# samd21_QFP_reference.net
KiCad netlist of a schematic drawn in EAGLE
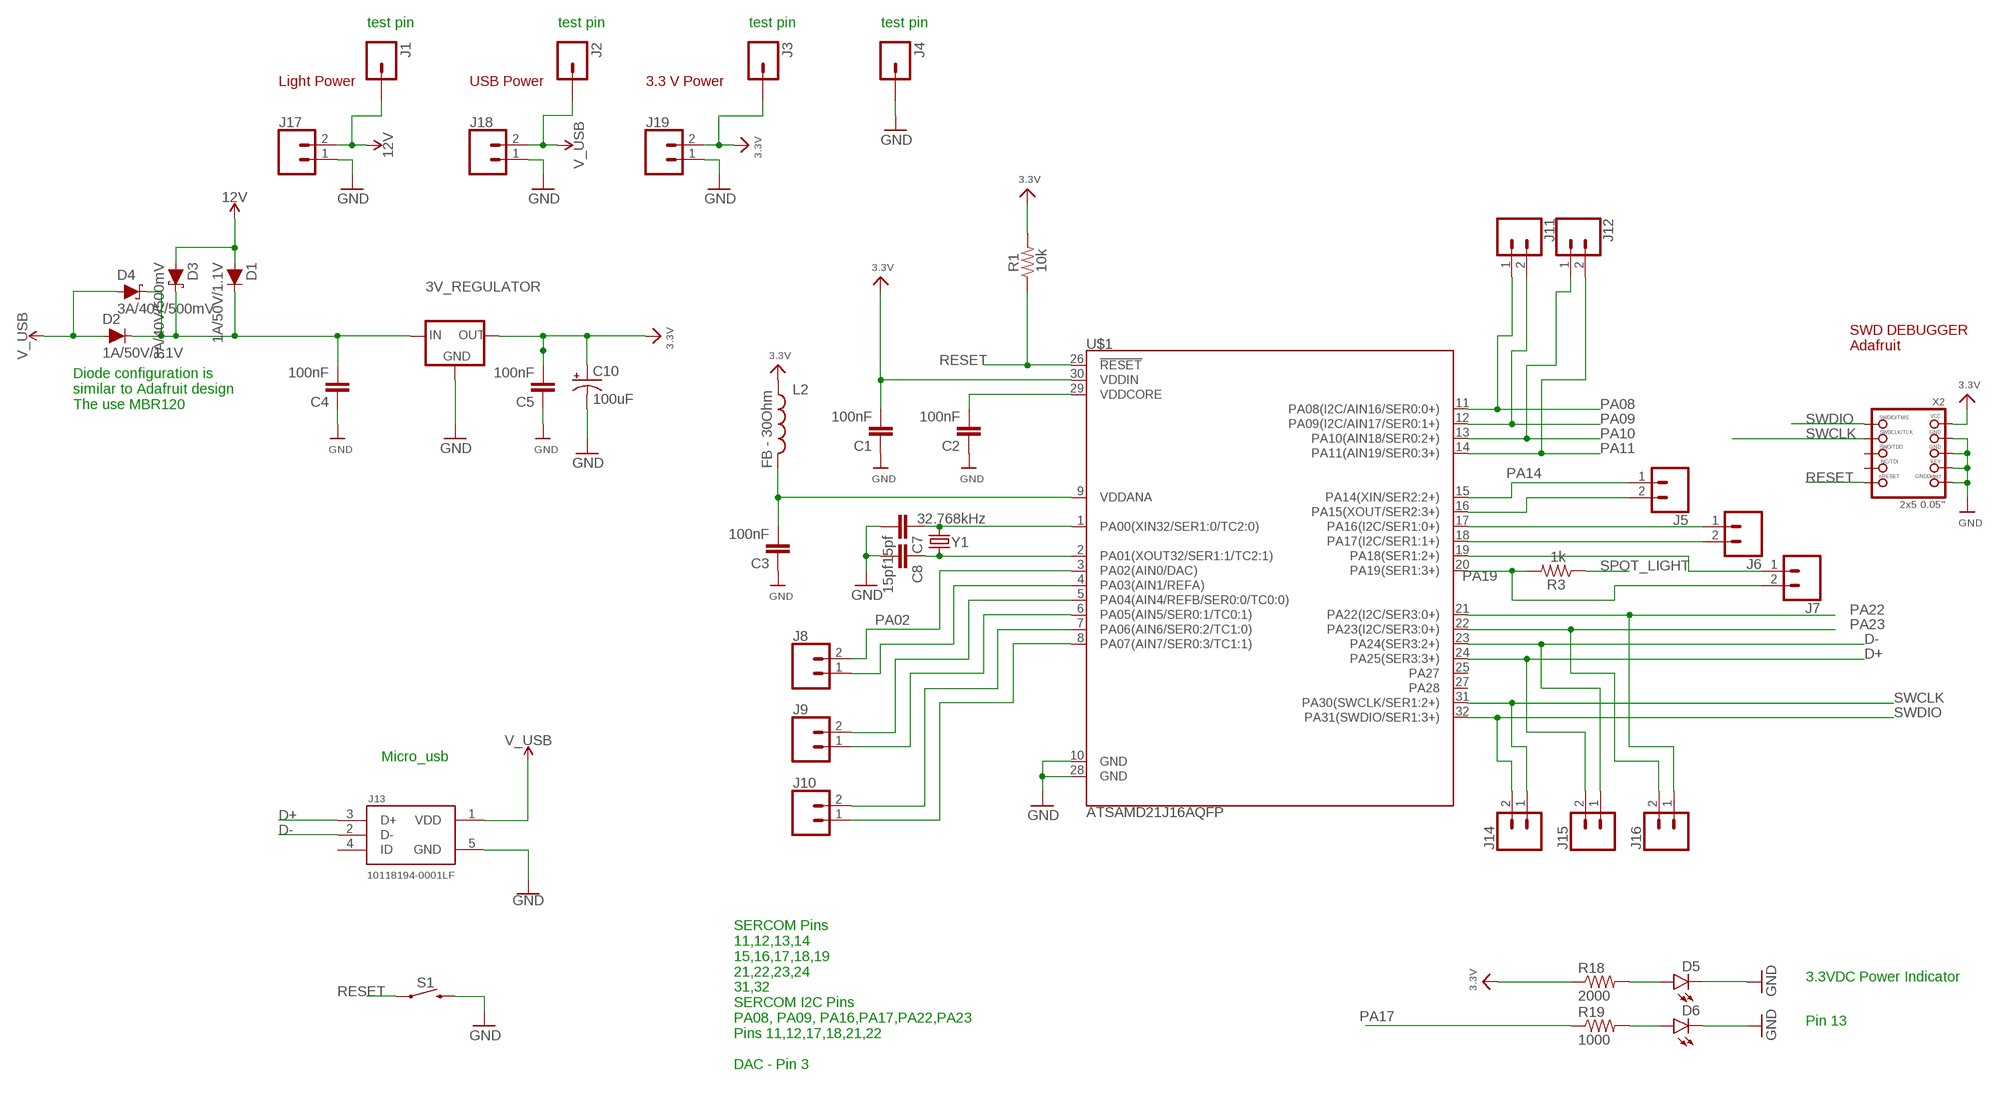
[diagram p0: schematic, sheet 1, part 1 of 2]
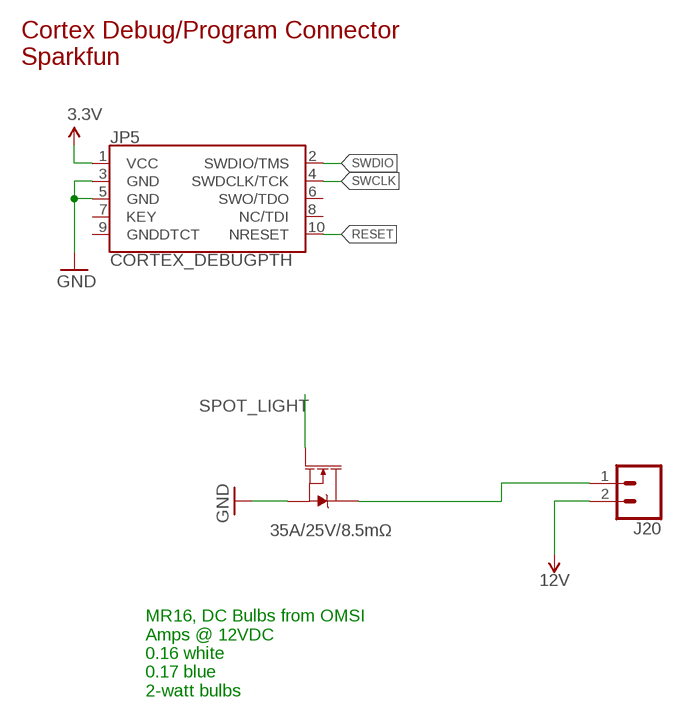
[diagram p1: schematic, sheet 1, part 2 of 2]

(export (version "E")
  (design (tool "Eeschema 10.0.6"))
  (components
    (comp (ref "3V_REGULATOR")
      (value "LDL1117_5V_REG")
      (footprint "eagle-import:SOT223")
      (libsource (lib "eagle-import") (part "LDL1117_5V_REG"))
    )
    (comp (ref "C1")
      (value "100nF")
      (footprint "eagle-import:0805")
      (libsource (lib "eagle-import") (part "10UF-0805-10V-10%"))
    )
    (comp (ref "C2")
      (value "100nF")
      (footprint "eagle-import:0805")
      (libsource (lib "eagle-import") (part "10UF-0805-10V-10%"))
    )
    (comp (ref "C3")
      (value "100nF")
      (footprint "eagle-import:0805")
      (libsource (lib "eagle-import") (part "10UF-0805-10V-10%"))
    )
    (comp (ref "C4")
      (value "100nF")
      (footprint "eagle-import:0805")
      (libsource (lib "eagle-import") (part "10UF-0805-10V-10%"))
    )
    (comp (ref "C5")
      (value "100nF")
      (footprint "eagle-import:0805")
      (libsource (lib "eagle-import") (part "10UF-0805-10V-10%"))
    )
    (comp (ref "C7")
      (value "15pf")
      (footprint "eagle-import:0805")
      (libsource (lib "eagle-import") (part "10UF-0805-10V-10%"))
    )
    (comp (ref "C8")
      (value "15pf")
      (footprint "eagle-import:0805")
      (libsource (lib "eagle-import") (part "10UF-0805-10V-10%"))
    )
    (comp (ref "C10")
      (value "100uF")
      (footprint "eagle-import:CPOL-RADIAL-2.5MM-6.5MM")
      (libsource (lib "eagle-import") (part "100UF-POLAR-RADIAL-2.5MM-25V-20%"))
    )
    (comp (ref "D1")
      (value "1A/50V/1.1V")
      (footprint "eagle-import:DIODE-1N4001")
      (libsource (lib "eagle-import") (part "DIODE-PTH"))
    )
    (comp (ref "D2")
      (value "1A/50V/1.1V")
      (footprint "eagle-import:DIODE-1N4001")
      (libsource (lib "eagle-import") (part "DIODE-PTH"))
    )
    (comp (ref "D3")
      (value "3A/40V/500mV")
      (footprint "eagle-import:SMA-DIODE")
      (libsource (lib "eagle-import") (part "DIODE-SCHOTTKY-B340A"))
    )
    (comp (ref "D4")
      (value "3A/40V/500mV")
      (footprint "eagle-import:SMA-DIODE")
      (libsource (lib "eagle-import") (part "DIODE-SCHOTTKY-B340A"))
    )
    (comp (ref "D5")
      (value "LED1206")
      (footprint "eagle-import:LED-1206")
      (libsource (lib "eagle-import") (part "LED1206"))
    )
    (comp (ref "D6")
      (value "LED1206")
      (footprint "eagle-import:LED-1206")
      (libsource (lib "eagle-import") (part "LED1206"))
    )
    (comp (ref "J1")
      (value "M01PTH")
      (footprint "eagle-import:1X01")
      (libsource (lib "eagle-import") (part "M01PTH"))
    )
    (comp (ref "J2")
      (value "M01PTH")
      (footprint "eagle-import:1X01")
      (libsource (lib "eagle-import") (part "M01PTH"))
    )
    (comp (ref "J3")
      (value "M01PTH")
      (footprint "eagle-import:1X01")
      (libsource (lib "eagle-import") (part "M01PTH"))
    )
    (comp (ref "J4")
      (value "M01PTH")
      (footprint "eagle-import:1X01")
      (libsource (lib "eagle-import") (part "M01PTH"))
    )
    (comp (ref "J5")
      (value "CONN_025MM")
      (footprint "eagle-import:SCREWTERMINAL-5MM-2")
      (libsource (lib "eagle-import") (part "CONN_025MM"))
    )
    (comp (ref "J6")
      (value "CONN_025MM")
      (footprint "eagle-import:SCREWTERMINAL-5MM-2")
      (libsource (lib "eagle-import") (part "CONN_025MM"))
    )
    (comp (ref "J7")
      (value "CONN_025MM")
      (footprint "eagle-import:SCREWTERMINAL-5MM-2")
      (libsource (lib "eagle-import") (part "CONN_025MM"))
    )
    (comp (ref "J8")
      (value "CONN_025MM")
      (footprint "eagle-import:SCREWTERMINAL-5MM-2")
      (libsource (lib "eagle-import") (part "CONN_025MM"))
    )
    (comp (ref "J9")
      (value "CONN_025MM")
      (footprint "eagle-import:SCREWTERMINAL-5MM-2")
      (libsource (lib "eagle-import") (part "CONN_025MM"))
    )
    (comp (ref "J10")
      (value "CONN_025MM")
      (footprint "eagle-import:SCREWTERMINAL-5MM-2")
      (libsource (lib "eagle-import") (part "CONN_025MM"))
    )
    (comp (ref "J11")
      (value "CONN_025MM")
      (footprint "eagle-import:SCREWTERMINAL-5MM-2")
      (libsource (lib "eagle-import") (part "CONN_025MM"))
    )
    (comp (ref "J12")
      (value "CONN_025MM")
      (footprint "eagle-import:SCREWTERMINAL-5MM-2")
      (libsource (lib "eagle-import") (part "CONN_025MM"))
    )
    (comp (ref "J13")
      (value "10118194-0001LF")
      (footprint "eagle-import:FRAMATOME_10118194-0001LF")
      (fields (field (name "MF") "Amphenol ICC"))
      (libsource (lib "eagle-import") (part "10118194-0001LF"))
    )
    (comp (ref "J14")
      (value "CONN_025MM")
      (footprint "eagle-import:SCREWTERMINAL-5MM-2")
      (libsource (lib "eagle-import") (part "CONN_025MM"))
    )
    (comp (ref "J15")
      (value "CONN_025MM")
      (footprint "eagle-import:SCREWTERMINAL-5MM-2")
      (libsource (lib "eagle-import") (part "CONN_025MM"))
    )
    (comp (ref "J16")
      (value "CONN_025MM")
      (footprint "eagle-import:SCREWTERMINAL-5MM-2")
      (libsource (lib "eagle-import") (part "CONN_025MM"))
    )
    (comp (ref "J17")
      (value "CONN_025MM")
      (footprint "eagle-import:SCREWTERMINAL-5MM-2")
      (libsource (lib "eagle-import") (part "CONN_025MM"))
    )
    (comp (ref "J18")
      (value "CONN_025MM")
      (footprint "eagle-import:SCREWTERMINAL-5MM-2")
      (libsource (lib "eagle-import") (part "CONN_025MM"))
    )
    (comp (ref "J19")
      (value "CONN_025MM")
      (footprint "eagle-import:SCREWTERMINAL-5MM-2")
      (libsource (lib "eagle-import") (part "CONN_025MM"))
    )
    (comp (ref "J20")
      (value "CONN_025MM")
      (footprint "eagle-import:SCREWTERMINAL-5MM-2")
      (libsource (lib "eagle-import") (part "CONN_025MM"))
    )
    (comp (ref "JP5")
      (value "CORTEX_DEBUGPTH")
      (footprint "eagle-import:2X5-PTH-1.27MM")
      (libsource (lib "eagle-import") (part "CORTEX_DEBUGPTH"))
    )
    (comp (ref "L2")
      (value "FB - 30Ohm")
      (footprint "eagle-import:0805@1")
      (libsource (lib "eagle-import") (part "INDUCTOR0805"))
    )
    (comp (ref "Q1")
      (value "35A/25V/8.5mΩ")
      (footprint "eagle-import:DPAK")
      (libsource (lib "eagle-import") (part "MOSFET-NCH-FDD8780"))
    )
    (comp (ref "R1")
      (value "10k")
      (footprint "eagle-import:0805")
      (libsource (lib "eagle-import") (part "RESISTOR0805"))
    )
    (comp (ref "R3")
      (value "1k")
      (footprint "eagle-import:0805")
      (libsource (lib "eagle-import") (part "RESISTOR0805"))
    )
    (comp (ref "R18")
      (value "2000")
      (footprint "eagle-import:0805")
      (libsource (lib "eagle-import") (part "RESISTOR0805-RES"))
    )
    (comp (ref "R19")
      (value "1000")
      (footprint "eagle-import:0805")
      (libsource (lib "eagle-import") (part "RESISTOR0805-RES"))
    )
    (comp (ref "S1")
      (value "MOMENTARY-SWITCH-SPST-PTH-6.0MM-KIT")
      (footprint "eagle-import:TACTILE_SWITCH_PTH_6.0MM_KIT")
      (libsource (lib "eagle-import") (part "MOMENTARY-SWITCH-SPST-PTH-6.0MM-KIT"))
    )
    (comp (ref "U$1")
      (value "ATSAMD21J16AQFP")
      (footprint "eagle-import:TQFP32-08")
      (libsource (lib "eagle-import") (part "ATSAMD21J16AQFP"))
    )
    (comp (ref "X2")
      (value "2x5 0.05\"")
      (footprint "eagle-import:2X05_1.27MM_BOX_POSTS")
      (libsource (lib "eagle-import") (part "JTAG-CORTEXBOXPOSTS"))
    )
    (comp (ref "Y1")
      (value "32.768kHz")
      (footprint "eagle-import:CRYSTAL-SMD-3.2X1.5MM")
      (libsource (lib "eagle-import") (part "CRYSTAL3.2X1.5MM"))
    )
  )
  (nets
    (net (code "1") (name "/D+") (class "Default")
      (node (ref "J13") (pin "3") (pinfunction "D+_3") (pintype "bidirectional"))
      (node (ref "J15") (pin "2") (pinfunction "2_2") (pintype "passive"))
      (node (ref "U$1") (pin "24") (pinfunction "PA25(SER3:3+)_24") (pintype "bidirectional"))
    )
    (net (code "2") (name "/D-") (class "Default")
      (node (ref "J13") (pin "2") (pinfunction "D-_2") (pintype "bidirectional"))
      (node (ref "J15") (pin "1") (pinfunction "1_1") (pintype "passive"))
      (node (ref "U$1") (pin "23") (pinfunction "PA24(SER3:2+)_23") (pintype "bidirectional"))
    )
    (net (code "3") (name "/PA02") (class "Default")
      (node (ref "J8") (pin "2") (pinfunction "2_2") (pintype "passive"))
      (node (ref "U$1") (pin "3") (pinfunction "PA02(AIN0/DAC)_3") (pintype "bidirectional"))
    )
    (net (code "4") (name "/PA08") (class "Default")
      (node (ref "J11") (pin "1") (pinfunction "1_1") (pintype "passive"))
      (node (ref "U$1") (pin "11") (pinfunction "PA08(I2C/AIN16/SER0:0+)_11") (pintype "bidirectional"))
    )
    (net (code "5") (name "/PA09") (class "Default")
      (node (ref "J11") (pin "2") (pinfunction "2_2") (pintype "passive"))
      (node (ref "U$1") (pin "12") (pinfunction "PA09(I2C/AIN17/SER0:1+)_12") (pintype "bidirectional"))
    )
    (net (code "6") (name "/PA10") (class "Default")
      (node (ref "J12") (pin "1") (pinfunction "1_1") (pintype "passive"))
      (node (ref "U$1") (pin "13") (pinfunction "PA10(AIN18/SER0:2+)_13") (pintype "bidirectional"))
    )
    (net (code "7") (name "/PA11") (class "Default")
      (node (ref "J12") (pin "2") (pinfunction "2_2") (pintype "passive"))
      (node (ref "U$1") (pin "14") (pinfunction "PA11(AIN19/SER0:3+)_14") (pintype "bidirectional"))
    )
    (net (code "8") (name "/PA14") (class "Default")
      (node (ref "J5") (pin "1") (pinfunction "1_1") (pintype "passive"))
      (node (ref "U$1") (pin "15") (pinfunction "PA14(XIN/SER2:2+)_15") (pintype "bidirectional"))
    )
    (net (code "9") (name "/PA17") (class "Default")
      (node (ref "J6") (pin "2") (pinfunction "2_2") (pintype "passive"))
      (node (ref "R19") (pin "1") (pinfunction "1_1") (pintype "passive"))
      (node (ref "U$1") (pin "18") (pinfunction "PA17(I2C/SER1:1+)_18") (pintype "bidirectional"))
    )
    (net (code "10") (name "/PA19") (class "Default")
      (node (ref "J7") (pin "2") (pinfunction "2_2") (pintype "passive"))
      (node (ref "R3") (pin "2") (pinfunction "2_2") (pintype "passive"))
      (node (ref "U$1") (pin "20") (pinfunction "PA19(SER1:3+)_20") (pintype "bidirectional"))
    )
    (net (code "11") (name "/PA22") (class "Default")
      (node (ref "J16") (pin "1") (pinfunction "1_1") (pintype "passive"))
      (node (ref "U$1") (pin "21") (pinfunction "PA22(I2C/SER3:0+)_21") (pintype "bidirectional"))
    )
    (net (code "12") (name "/PA23") (class "Default")
      (node (ref "J16") (pin "2") (pinfunction "2_2") (pintype "passive"))
      (node (ref "U$1") (pin "22") (pinfunction "PA23(I2C/SER3:0+)_22") (pintype "bidirectional"))
    )
    (net (code "13") (name "/SPOT_LIGHT") (class "Default")
      (node (ref "Q1") (pin "1") (pinfunction "G_1") (pintype "bidirectional"))
      (node (ref "R3") (pin "1") (pinfunction "1_1") (pintype "passive"))
    )
    (net (code "14") (name "3.3V") (class "Default")
      (node (ref "3V_REGULATOR") (pin "2") (pinfunction "OUT_2") (pintype "passive"))
      (node (ref "3V_REGULATOR") (pin "4") (pinfunction "OUT_4") (pintype "passive"))
      (node (ref "C1") (pin "2") (pinfunction "2_2") (pintype "passive"))
      (node (ref "C10") (pin "1") (pinfunction "+_1") (pintype "passive"))
      (node (ref "C5") (pin "2") (pinfunction "2_2") (pintype "passive"))
      (node (ref "J19") (pin "2") (pinfunction "2_2") (pintype "passive"))
      (node (ref "J3") (pin "1") (pinfunction "1_1") (pintype "passive"))
      (node (ref "JP5") (pin "1") (pinfunction "VCC_1") (pintype "bidirectional"))
      (node (ref "L2") (pin "1") (pinfunction "1_1") (pintype "passive"))
      (node (ref "R1") (pin "2") (pinfunction "2_2") (pintype "passive"))
      (node (ref "R18") (pin "1") (pinfunction "1_1") (pintype "passive"))
      (node (ref "U$1") (pin "30") (pinfunction "VDDIN_30") (pintype "bidirectional"))
      (node (ref "X2") (pin "1") (pinfunction "VCC_1") (pintype "power_in"))
    )
    (net (code "15") (name "12V") (class "Default")
      (node (ref "D1") (pin "A") (pinfunction "A_A") (pintype "passive"))
      (node (ref "D3") (pin "A") (pinfunction "A_A") (pintype "passive"))
      (node (ref "J1") (pin "1") (pinfunction "1_1") (pintype "passive"))
      (node (ref "J17") (pin "2") (pinfunction "2_2") (pintype "passive"))
      (node (ref "J20") (pin "2") (pinfunction "2_2") (pintype "passive"))
    )
    (net (code "16") (name "GND") (class "Default")
      (node (ref "3V_REGULATOR") (pin "1") (pinfunction "GND_1") (pintype "input"))
      (node (ref "C1") (pin "1") (pinfunction "1_1") (pintype "passive"))
      (node (ref "C10") (pin "2") (pinfunction "-_2") (pintype "passive"))
      (node (ref "C2") (pin "1") (pinfunction "1_1") (pintype "passive"))
      (node (ref "C3") (pin "1") (pinfunction "1_1") (pintype "passive"))
      (node (ref "C4") (pin "1") (pinfunction "1_1") (pintype "passive"))
      (node (ref "C5") (pin "1") (pinfunction "1_1") (pintype "passive"))
      (node (ref "C7") (pin "2") (pinfunction "2_2") (pintype "passive"))
      (node (ref "C8") (pin "2") (pinfunction "2_2") (pintype "passive"))
      (node (ref "D5") (pin "C") (pinfunction "C_C") (pintype "passive"))
      (node (ref "D6") (pin "C") (pinfunction "C_C") (pintype "passive"))
      (node (ref "J13") (pin "5") (pinfunction "GND_5") (pintype "power_in"))
      (node (ref "J17") (pin "1") (pinfunction "1_1") (pintype "passive"))
      (node (ref "J18") (pin "1") (pinfunction "1_1") (pintype "passive"))
      (node (ref "J19") (pin "1") (pinfunction "1_1") (pintype "passive"))
      (node (ref "J4") (pin "1") (pinfunction "1_1") (pintype "passive"))
      (node (ref "JP5") (pin "3") (pinfunction "GND_3") (pintype "bidirectional"))
      (node (ref "JP5") (pin "5") (pinfunction "GND_5") (pintype "bidirectional"))
      (node (ref "Q1") (pin "3") (pinfunction "S_3") (pintype "bidirectional"))
      (node (ref "S1") (pin "3") (pinfunction "2_3") (pintype "passive"))
      (node (ref "U$1") (pin "10") (pinfunction "GND_10") (pintype "bidirectional"))
      (node (ref "U$1") (pin "28") (pinfunction "GND_28") (pintype "bidirectional"))
      (node (ref "X2") (pin "3") (pinfunction "GND_3") (pintype "power_in"))
      (node (ref "X2") (pin "5") (pinfunction "GND_5") (pintype "power_in"))
      (node (ref "X2") (pin "7") (pinfunction "KEY_7") (pintype "bidirectional"))
      (node (ref "X2") (pin "9") (pinfunction "GNDDETECT_9") (pintype "bidirectional"))
    )
    (net (code "17") (name "Net-(3V_REGULATOR-IN)") (class "Default")
      (node (ref "3V_REGULATOR") (pin "3") (pinfunction "IN_3") (pintype "input"))
      (node (ref "C4") (pin "2") (pinfunction "2_2") (pintype "passive"))
      (node (ref "D1") (pin "C") (pinfunction "C_C") (pintype "passive"))
      (node (ref "D2") (pin "C") (pinfunction "C_C") (pintype "passive"))
      (node (ref "D3") (pin "C") (pinfunction "C_C") (pintype "passive"))
      (node (ref "D4") (pin "C") (pinfunction "C_C") (pintype "passive"))
    )
    (net (code "18") (name "Net-(D5-PadA)") (class "Default")
      (node (ref "D5") (pin "A") (pinfunction "A_A") (pintype "passive"))
      (node (ref "R18") (pin "2") (pinfunction "2_2") (pintype "passive"))
    )
    (net (code "19") (name "Net-(D6-PadA)") (class "Default")
      (node (ref "D6") (pin "A") (pinfunction "A_A") (pintype "passive"))
      (node (ref "R19") (pin "2") (pinfunction "2_2") (pintype "passive"))
    )
    (net (code "20") (name "Net-(Q1-D)") (class "Default")
      (node (ref "J20") (pin "1") (pinfunction "1_1") (pintype "passive"))
      (node (ref "Q1") (pin "4") (pinfunction "D_4") (pintype "bidirectional"))
    )
    (net (code "21") (name "Net-(U$1-PA00(XIN32{slash}SER1:0{slash}TC2:0))") (class "Default")
      (node (ref "C7") (pin "1") (pinfunction "1_1") (pintype "passive"))
      (node (ref "U$1") (pin "1") (pinfunction "PA00(XIN32/SER1:0/TC2:0)_1") (pintype "bidirectional"))
      (node (ref "Y1") (pin "P$2") (pinfunction "2_P$2") (pintype "passive"))
    )
    (net (code "22") (name "Net-(U$1-PA01(XOUT32{slash}SER1:1{slash}TC2:1))") (class "Default")
      (node (ref "C8") (pin "1") (pinfunction "1_1") (pintype "passive"))
      (node (ref "U$1") (pin "2") (pinfunction "PA01(XOUT32/SER1:1/TC2:1)_2") (pintype "bidirectional"))
      (node (ref "Y1") (pin "P$1") (pinfunction "1_P$1") (pintype "passive"))
    )
    (net (code "23") (name "Net-(U$1-PA03(AIN1{slash}REFA))") (class "Default")
      (node (ref "J8") (pin "1") (pinfunction "1_1") (pintype "passive"))
      (node (ref "U$1") (pin "4") (pinfunction "PA03(AIN1/REFA)_4") (pintype "bidirectional"))
    )
    (net (code "24") (name "Net-(U$1-PA04(AIN4{slash}REFB{slash}SER0:0{slash}TC0:0))") (class "Default")
      (node (ref "J9") (pin "2") (pinfunction "2_2") (pintype "passive"))
      (node (ref "U$1") (pin "5") (pinfunction "PA04(AIN4/REFB/SER0:0/TC0:0)_5") (pintype "bidirectional"))
    )
    (net (code "25") (name "Net-(U$1-PA05(AIN5{slash}SER0:1{slash}TC0:1))") (class "Default")
      (node (ref "J9") (pin "1") (pinfunction "1_1") (pintype "passive"))
      (node (ref "U$1") (pin "6") (pinfunction "PA05(AIN5/SER0:1/TC0:1)_6") (pintype "bidirectional"))
    )
    (net (code "26") (name "Net-(U$1-PA06(AIN6{slash}SER0:2{slash}TC1:0))") (class "Default")
      (node (ref "J10") (pin "2") (pinfunction "2_2") (pintype "passive"))
      (node (ref "U$1") (pin "7") (pinfunction "PA06(AIN6/SER0:2/TC1:0)_7") (pintype "bidirectional"))
    )
    (net (code "27") (name "Net-(U$1-PA07(AIN7{slash}SER0:3{slash}TC1:1))") (class "Default")
      (node (ref "J10") (pin "1") (pinfunction "1_1") (pintype "passive"))
      (node (ref "U$1") (pin "8") (pinfunction "PA07(AIN7/SER0:3/TC1:1)_8") (pintype "bidirectional"))
    )
    (net (code "28") (name "Net-(U$1-PA15(XOUT{slash}SER2:3+))") (class "Default")
      (node (ref "J5") (pin "2") (pinfunction "2_2") (pintype "passive"))
      (node (ref "U$1") (pin "16") (pinfunction "PA15(XOUT/SER2:3+)_16") (pintype "bidirectional"))
    )
    (net (code "29") (name "Net-(U$1-PA16(I2C{slash}SER1:0+))") (class "Default")
      (node (ref "J6") (pin "1") (pinfunction "1_1") (pintype "passive"))
      (node (ref "U$1") (pin "17") (pinfunction "PA16(I2C/SER1:0+)_17") (pintype "bidirectional"))
    )
    (net (code "30") (name "Net-(U$1-PA18(SER1:2+))") (class "Default")
      (node (ref "J7") (pin "1") (pinfunction "1_1") (pintype "passive"))
      (node (ref "U$1") (pin "19") (pinfunction "PA18(SER1:2+)_19") (pintype "bidirectional"))
    )
    (net (code "31") (name "Net-(U$1-VDDANA)") (class "Default")
      (node (ref "C3") (pin "2") (pinfunction "2_2") (pintype "passive"))
      (node (ref "L2") (pin "2") (pinfunction "2_2") (pintype "passive"))
      (node (ref "U$1") (pin "9") (pinfunction "VDDANA_9") (pintype "bidirectional"))
    )
    (net (code "32") (name "Net-(U$1-VDDCORE)") (class "Default")
      (node (ref "C2") (pin "2") (pinfunction "2_2") (pintype "passive"))
      (node (ref "U$1") (pin "29") (pinfunction "VDDCORE_29") (pintype "bidirectional"))
    )
    (net (code "33") (name "RESET") (class "Default")
      (node (ref "JP5") (pin "10") (pinfunction "NRESET_10") (pintype "bidirectional"))
      (node (ref "R1") (pin "1") (pinfunction "1_1") (pintype "passive"))
      (node (ref "S1") (pin "1") (pinfunction "1_1") (pintype "passive"))
      (node (ref "U$1") (pin "26") (pinfunction "~{RESET}_26") (pintype "bidirectional"))
      (node (ref "X2") (pin "10") (pinfunction "NRESET_10") (pintype "bidirectional"))
    )
    (net (code "34") (name "SWCLK") (class "Default")
      (node (ref "J14") (pin "1") (pinfunction "1_1") (pintype "passive"))
      (node (ref "JP5") (pin "4") (pinfunction "SWDCLK/TCK_4") (pintype "bidirectional"))
      (node (ref "U$1") (pin "31") (pinfunction "PA30(SWCLK/SER1:2+)_31") (pintype "bidirectional"))
      (node (ref "X2") (pin "4") (pinfunction "SWDCLK_4") (pintype "bidirectional"))
    )
    (net (code "35") (name "SWDIO") (class "Default")
      (node (ref "J14") (pin "2") (pinfunction "2_2") (pintype "passive"))
      (node (ref "JP5") (pin "2") (pinfunction "SWDIO/TMS_2") (pintype "bidirectional"))
      (node (ref "U$1") (pin "32") (pinfunction "PA31(SWDIO/SER1:3+)_32") (pintype "bidirectional"))
      (node (ref "X2") (pin "2") (pinfunction "SWDIO_2") (pintype "bidirectional"))
    )
    (net (code "36") (name "V_USB") (class "Default")
      (node (ref "D2") (pin "A") (pinfunction "A_A") (pintype "passive"))
      (node (ref "D4") (pin "A") (pinfunction "A_A") (pintype "passive"))
      (node (ref "J13") (pin "1") (pinfunction "VDD_1") (pintype "power_in"))
      (node (ref "J18") (pin "2") (pinfunction "2_2") (pintype "passive"))
      (node (ref "J2") (pin "1") (pinfunction "1_1") (pintype "passive"))
    )
    (net (code "37") (name "unconnected-(J13-ID-Pad4)") (class "Default")
      (node (ref "J13") (pin "4") (pinfunction "ID_4") (pintype "passive"))
    )
    (net (code "38") (name "unconnected-(JP5-GNDDTCT-Pad9)") (class "Default")
      (node (ref "JP5") (pin "9") (pinfunction "GNDDTCT_9") (pintype "bidirectional"))
    )
    (net (code "39") (name "unconnected-(JP5-KEY-Pad7)") (class "Default")
      (node (ref "JP5") (pin "7") (pinfunction "KEY_7") (pintype "bidirectional"))
    )
    (net (code "40") (name "unconnected-(JP5-NC{slash}TDI-Pad8)") (class "Default")
      (node (ref "JP5") (pin "8") (pinfunction "NC/TDI_8") (pintype "bidirectional"))
    )
    (net (code "41") (name "unconnected-(JP5-SWO{slash}TDO-Pad6)") (class "Default")
      (node (ref "JP5") (pin "6") (pinfunction "SWO/TDO_6") (pintype "bidirectional"))
    )
    (net (code "42") (name "unconnected-(U$1-PA27-Pad25)") (class "Default")
      (node (ref "U$1") (pin "25") (pinfunction "PA27_25") (pintype "bidirectional"))
    )
    (net (code "43") (name "unconnected-(U$1-PA28-Pad27)") (class "Default")
      (node (ref "U$1") (pin "27") (pinfunction "PA28_27") (pintype "bidirectional"))
    )
    (net (code "44") (name "unconnected-(X2-SWO-Pad6)") (class "Default")
      (node (ref "X2") (pin "6") (pinfunction "SWO_6") (pintype "bidirectional"))
    )
    (net (code "45") (name "unconnected-(X2-TDI-Pad8)") (class "Default")
      (node (ref "X2") (pin "8") (pinfunction "TDI_8") (pintype "bidirectional"))
    )
  )
)
